# BNO055_Host.net
KiCad netlist of a schematic drawn in Altium Designer
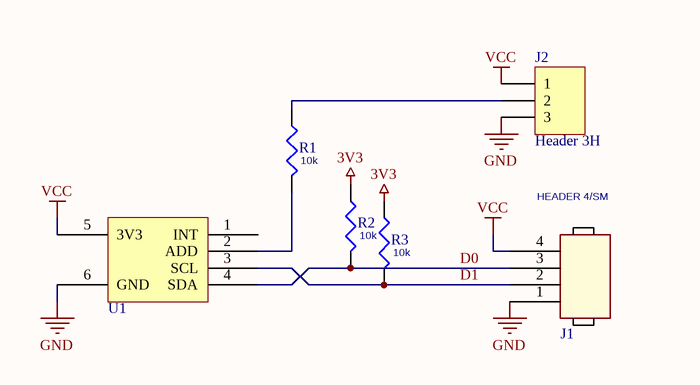
[diagram p0: BNO055 Host.SchDoc]

(export (version "E")
  (design (tool "Eeschema 10.0.6"))
  (components
    (comp (ref "J1")
      (value "HEADER 4/SM")
      (footprint "61900411021 - flip")
      (libsource (lib "SLEEPTRACK2_PHASE3_Library") (part "HEADER 4/SM"))
    )
    (comp (ref "J2")
      (value "Header 3H")
      (footprint "Phase4:SolderJumper")
      (description "Header, 3-Pin, Right Angle")
      (fields (field (name "PUBLISHER") "Altium Limited"))
      (libsource (lib "Miscellaneous Connectors") (part "Header 3H"))
    )
    (comp (ref "R1")
      (value "10k")
      (footprint "RESC402N")
      (description "RES SMD 10K OHM 1% 1/16W 0402")
      (libsource (lib "SLEEPTRACK2_PHASE3_Library") (part "RC0402FR-0710KL"))
    )
    (comp (ref "R2")
      (value "10k")
      (footprint "RESC402N")
      (description "RES SMD 10K OHM 1% 1/16W 0402")
      (libsource (lib "SLEEPTRACK2_PHASE3_Library") (part "RC0402FR-0710KL"))
    )
    (comp (ref "R3")
      (value "10k")
      (footprint "RESC402N")
      (description "RES SMD 10K OHM 1% 1/16W 0402")
      (libsource (lib "SLEEPTRACK2_PHASE3_Library") (part "RC0402FR-0710KL"))
    )
    (comp (ref "U1")
      (value "BNO055")
      (footprint "BNO055")
      (description "PESKY PRODUCTS BNO-055 NANO BREAKOUT BOARD")
      (libsource (lib "SLEEPTRACK2_PHASE3_Library") (part "BNO055 Nano"))
    )
  )
  (nets
    (net (code "1") (name "/D0") (class "Default")
      (node (ref "J1") (pin "3") (pinfunction "3_3") (pintype "passive"))
      (node (ref "R2") (pin "2") (pinfunction "2_2") (pintype "passive"))
      (node (ref "U1") (pin "4") (pinfunction "SDA_4") (pintype "passive"))
    )
    (net (code "2") (name "/D1") (class "Default")
      (node (ref "J1") (pin "2") (pinfunction "2_2") (pintype "passive"))
      (node (ref "R3") (pin "2") (pinfunction "2_2") (pintype "passive"))
      (node (ref "U1") (pin "3") (pinfunction "SCL_3") (pintype "passive"))
    )
    (net (code "3") (name "3V3") (class "Default")
      (node (ref "R2") (pin "1") (pinfunction "1_1") (pintype "passive"))
      (node (ref "R3") (pin "1") (pinfunction "1_1") (pintype "passive"))
    )
    (net (code "4") (name "GND") (class "Default")
      (node (ref "J1") (pin "1") (pinfunction "1_1") (pintype "passive"))
      (node (ref "J2") (pin "3") (pinfunction "3_3") (pintype "passive"))
      (node (ref "U1") (pin "6") (pinfunction "GND_6") (pintype "passive"))
    )
    (net (code "5") (name "Net-(J2-Pad2)") (class "Default")
      (node (ref "J2") (pin "2") (pinfunction "2_2") (pintype "passive"))
      (node (ref "R1") (pin "1") (pinfunction "1_1") (pintype "passive"))
    )
    (net (code "6") (name "Net-(U1-ADD)") (class "Default")
      (node (ref "R1") (pin "2") (pinfunction "2_2") (pintype "passive"))
      (node (ref "U1") (pin "2") (pinfunction "ADD_2") (pintype "passive"))
    )
    (net (code "7") (name "VCC") (class "Default")
      (node (ref "J1") (pin "4") (pinfunction "4_4") (pintype "passive"))
      (node (ref "J2") (pin "1") (pinfunction "1_1") (pintype "passive"))
      (node (ref "U1") (pin "5") (pinfunction "3V3_5") (pintype "passive"))
    )
    (net (code "8") (name "unconnected-(U1-INT-Pad1)") (class "Default")
      (node (ref "U1") (pin "1") (pinfunction "INT_1") (pintype "passive"))
    )
  )
)
